# control_board.net
KiCad netlist of a schematic drawn in EAGLE
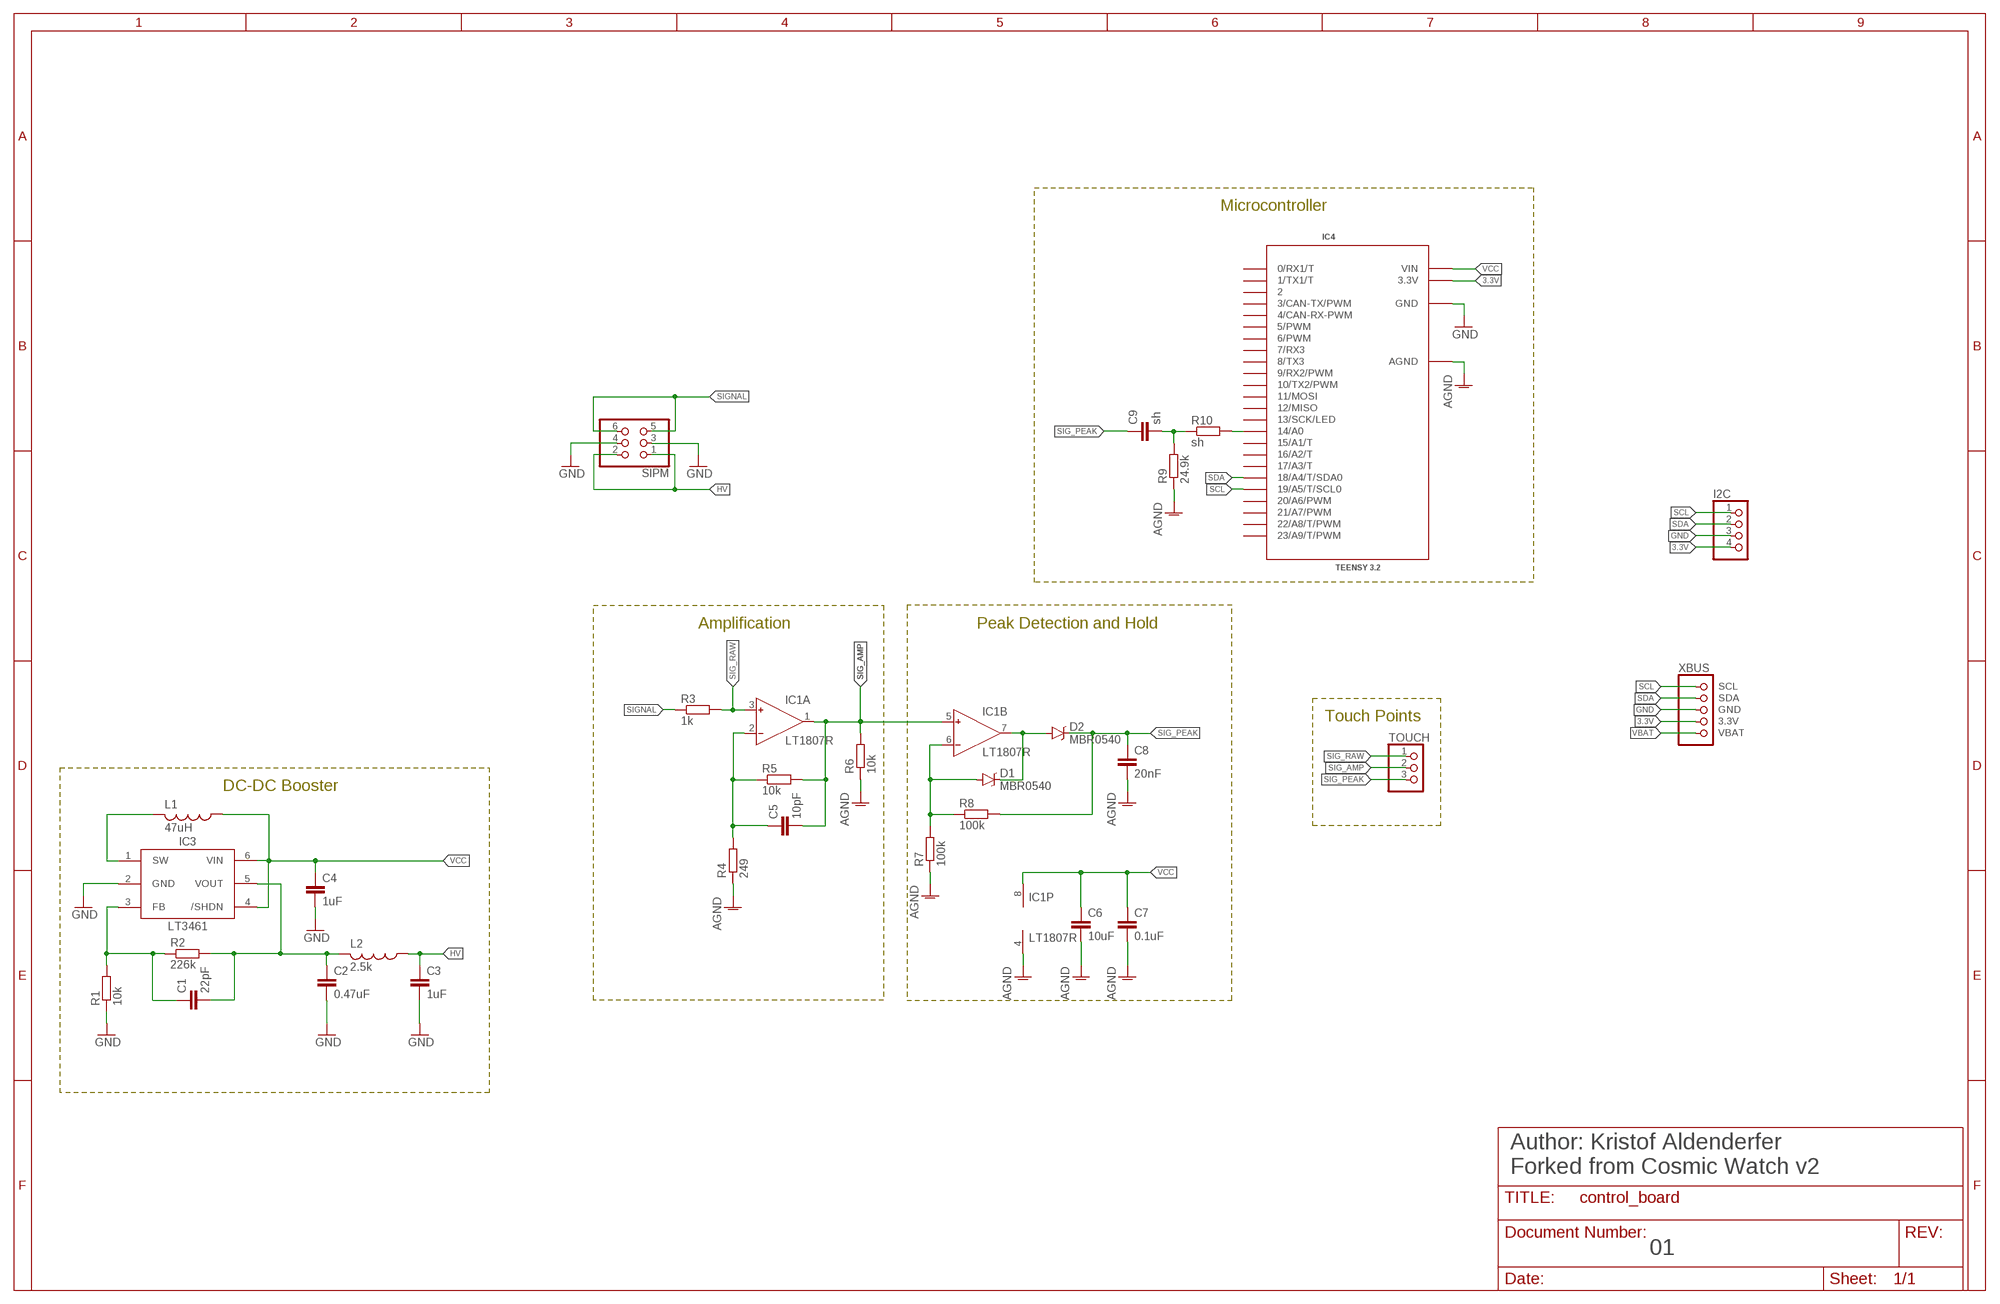
[diagram p0: schematic, sheet 1]

(export (version "E")
  (design (tool "Eeschema 10.0.6"))
  (components
    (comp (ref "C1")
      (value "22pF")
      (footprint "eagle-import:C0805K")
      (libsource (lib "eagle-import") (part "C-EUC0805K"))
    )
    (comp (ref "C2")
      (value "0.47uF")
      (footprint "eagle-import:C0805K")
      (libsource (lib "eagle-import") (part "C-EUC0805K"))
    )
    (comp (ref "C3")
      (value "1uF")
      (footprint "eagle-import:C0805K")
      (libsource (lib "eagle-import") (part "C-EUC0805K"))
    )
    (comp (ref "C4")
      (value "1uF")
      (footprint "eagle-import:C0805K")
      (libsource (lib "eagle-import") (part "C-EUC0805K"))
    )
    (comp (ref "C5")
      (value "10pF")
      (footprint "eagle-import:C0805K")
      (libsource (lib "eagle-import") (part "C-EUC0805K"))
    )
    (comp (ref "C6")
      (value "10uF")
      (footprint "eagle-import:C0805K")
      (libsource (lib "eagle-import") (part "C-EUC0805K"))
    )
    (comp (ref "C7")
      (value "0.1uF")
      (footprint "eagle-import:C0805K")
      (libsource (lib "eagle-import") (part "C-EUC0805K"))
    )
    (comp (ref "C8")
      (value "20nF")
      (footprint "eagle-import:C0805K")
      (libsource (lib "eagle-import") (part "C-EUC0805K"))
    )
    (comp (ref "C9")
      (value "sh")
      (footprint "eagle-import:C0805K")
      (libsource (lib "eagle-import") (part "C-EUC0805K"))
    )
    (comp (ref "D1")
      (value "MBR0540")
      (footprint "eagle-import:SMA-DIODE")
      (libsource (lib "eagle-import") (part "DIODE-SCHOTTKY-B340A"))
    )
    (comp (ref "D2")
      (value "MBR0540")
      (footprint "eagle-import:SMA-DIODE")
      (libsource (lib "eagle-import") (part "DIODE-SCHOTTKY-B340A"))
    )
    (comp (ref "I2C")
      (value "PINHD-1X4")
      (footprint "eagle-import:1X04")
      (libsource (lib "eagle-import") (part "PINHD-1X4"))
    )
    (comp (ref "IC1")
      (value "LT1807R")
      (footprint "eagle-import:SO8")
      (fields (field (name "MF") "ALTERA CORPORATION") (field (name "MPN") "AD746JRZ"))
      (libsource (lib "eagle-import") (part "LT1807R"))
    )
    (comp (ref "IC3")
      (value "LT3461")
      (footprint "eagle-import:SOT23-6")
      (libsource (lib "eagle-import") (part "LT3461"))
    )
    (comp (ref "IC4")
      (value "TEENSY 3.2")
      (footprint "eagle-import:TEENSY_3.2_NO_BOTTOM")
      (libsource (lib "eagle-import") (part "TEENSY_3.2_NO_BOTTOM"))
    )
    (comp (ref "L1")
      (value "47uH")
      (footprint "eagle-import:L2012C")
      (libsource (lib "eagle-import") (part "L-USL2012C"))
    )
    (comp (ref "L2")
      (value "2.5k")
      (footprint "eagle-import:L2012C")
      (libsource (lib "eagle-import") (part "L-USL2012C"))
    )
    (comp (ref "R1")
      (value "10k")
      (footprint "eagle-import:M0805")
      (libsource (lib "eagle-import") (part "R-EU_M0805"))
    )
    (comp (ref "R2")
      (value "226k")
      (footprint "eagle-import:M0805")
      (libsource (lib "eagle-import") (part "R-EU_M0805"))
    )
    (comp (ref "R3")
      (value "1k")
      (footprint "eagle-import:M0805")
      (libsource (lib "eagle-import") (part "R-EU_M0805"))
    )
    (comp (ref "R4")
      (value "249")
      (footprint "eagle-import:M0805")
      (libsource (lib "eagle-import") (part "R-EU_M0805"))
    )
    (comp (ref "R5")
      (value "10k")
      (footprint "eagle-import:M0805")
      (libsource (lib "eagle-import") (part "R-EU_M0805"))
    )
    (comp (ref "R6")
      (value "10k")
      (footprint "eagle-import:M0805")
      (libsource (lib "eagle-import") (part "R-EU_M0805"))
    )
    (comp (ref "R7")
      (value "100k")
      (footprint "eagle-import:M0805")
      (libsource (lib "eagle-import") (part "R-EU_M0805"))
    )
    (comp (ref "R8")
      (value "100k")
      (footprint "eagle-import:M0805")
      (libsource (lib "eagle-import") (part "R-EU_M0805"))
    )
    (comp (ref "R9")
      (value "24.9k")
      (footprint "eagle-import:M0805")
      (libsource (lib "eagle-import") (part "R-EU_M0805"))
    )
    (comp (ref "R10")
      (value "sh")
      (footprint "eagle-import:M0805")
      (libsource (lib "eagle-import") (part "R-EU_M0805"))
    )
    (comp (ref "SIPM")
      (value "PINHD-2X3")
      (footprint "eagle-import:2X03")
      (libsource (lib "eagle-import") (part "PINHD-2X3"))
    )
    (comp (ref "TOUCH")
      (value "PINHD-1X3")
      (footprint "eagle-import:1X03")
      (libsource (lib "eagle-import") (part "PINHD-1X3"))
    )
    (comp (ref "XBUS")
      (value "XINABOX-XBUS")
      (footprint "eagle-import:XBUS_1X05_PAD")
      (libsource (lib "eagle-import") (part "XINABOX-XBUS"))
    )
  )
  (nets
    (net (code "1") (name "3.3V") (class "Default")
      (node (ref "I2C") (pin "4") (pinfunction "4_4") (pintype "passive"))
      (node (ref "IC4") (pin "3.3V") (pinfunction "3.3V_3.3V") (pintype "power_in"))
      (node (ref "XBUS") (pin "P4B") (pinfunction "3.3V_P4B") (pintype "passive"))
      (node (ref "XBUS") (pin "P4T") (pinfunction "3.3V_P4T") (pintype "passive"))
    )
    (net (code "2") (name "AGND") (class "Default")
      (node (ref "C6") (pin "2") (pinfunction "2_2") (pintype "passive"))
      (node (ref "C7") (pin "2") (pinfunction "2_2") (pintype "passive"))
      (node (ref "C8") (pin "2") (pinfunction "2_2") (pintype "passive"))
      (node (ref "IC1") (pin "4") (pinfunction "V-_4") (pintype "power_in"))
      (node (ref "IC4") (pin "AGND") (pinfunction "AGND_AGND") (pintype "power_in"))
      (node (ref "R4") (pin "1") (pinfunction "1_1") (pintype "passive"))
      (node (ref "R6") (pin "1") (pinfunction "1_1") (pintype "passive"))
      (node (ref "R7") (pin "1") (pinfunction "1_1") (pintype "passive"))
      (node (ref "R9") (pin "1") (pinfunction "1_1") (pintype "passive"))
    )
    (net (code "3") (name "GND") (class "Default")
      (node (ref "C2") (pin "2") (pinfunction "2_2") (pintype "passive"))
      (node (ref "C3") (pin "2") (pinfunction "2_2") (pintype "passive"))
      (node (ref "C4") (pin "2") (pinfunction "2_2") (pintype "passive"))
      (node (ref "I2C") (pin "3") (pinfunction "3_3") (pintype "passive"))
      (node (ref "IC3") (pin "2") (pinfunction "GND_2") (pintype "power_in"))
      (node (ref "IC4") (pin "GND") (pinfunction "GND_GND") (pintype "power_in"))
      (node (ref "R1") (pin "1") (pinfunction "1_1") (pintype "passive"))
      (node (ref "SIPM") (pin "3") (pinfunction "3_3") (pintype "passive"))
      (node (ref "SIPM") (pin "4") (pinfunction "4_4") (pintype "passive"))
      (node (ref "XBUS") (pin "P3B") (pinfunction "GND_P3B") (pintype "passive"))
      (node (ref "XBUS") (pin "P3T") (pinfunction "GND_P3T") (pintype "passive"))
    )
    (net (code "4") (name "HV") (class "Default")
      (node (ref "C3") (pin "1") (pinfunction "1_1") (pintype "passive"))
      (node (ref "L2") (pin "1") (pinfunction "1_1") (pintype "passive"))
      (node (ref "SIPM") (pin "1") (pinfunction "1_1") (pintype "passive"))
      (node (ref "SIPM") (pin "2") (pinfunction "2_2") (pintype "passive"))
    )
    (net (code "5") (name "Net-(C9-Pad2)") (class "Default")
      (node (ref "C9") (pin "2") (pinfunction "2_2") (pintype "passive"))
      (node (ref "R10") (pin "1") (pinfunction "1_1") (pintype "passive"))
      (node (ref "R9") (pin "2") (pinfunction "2_2") (pintype "passive"))
    )
    (net (code "6") (name "Net-(IC1A-IN-)") (class "Default")
      (node (ref "C5") (pin "1") (pinfunction "1_1") (pintype "passive"))
      (node (ref "IC1") (pin "2") (pinfunction "IN-_2") (pintype "input"))
      (node (ref "R4") (pin "2") (pinfunction "2_2") (pintype "passive"))
      (node (ref "R5") (pin "1") (pinfunction "1_1") (pintype "passive"))
    )
    (net (code "7") (name "Net-(IC1B-IN-)") (class "Default")
      (node (ref "D1") (pin "A") (pinfunction "A_A") (pintype "passive"))
      (node (ref "IC1") (pin "6") (pinfunction "IN-_6") (pintype "input"))
      (node (ref "R7") (pin "2") (pinfunction "2_2") (pintype "passive"))
      (node (ref "R8") (pin "1") (pinfunction "1_1") (pintype "passive"))
    )
    (net (code "8") (name "Net-(IC1B-OUT)") (class "Default")
      (node (ref "D1") (pin "C") (pinfunction "C_C") (pintype "passive"))
      (node (ref "D2") (pin "A") (pinfunction "A_A") (pintype "passive"))
      (node (ref "IC1") (pin "7") (pinfunction "OUT_7") (pintype "output"))
    )
    (net (code "9") (name "Net-(IC3-FB)") (class "Default")
      (node (ref "C1") (pin "1") (pinfunction "1_1") (pintype "passive"))
      (node (ref "IC3") (pin "3") (pinfunction "FB_3") (pintype "input"))
      (node (ref "R1") (pin "2") (pinfunction "2_2") (pintype "passive"))
      (node (ref "R2") (pin "1") (pinfunction "1_1") (pintype "passive"))
    )
    (net (code "10") (name "Net-(IC3-SW)") (class "Default")
      (node (ref "IC3") (pin "1") (pinfunction "SW_1") (pintype "output"))
      (node (ref "L1") (pin "2") (pinfunction "2_2") (pintype "passive"))
    )
    (net (code "11") (name "Net-(IC3-VOUT)") (class "Default")
      (node (ref "C1") (pin "2") (pinfunction "2_2") (pintype "passive"))
      (node (ref "C2") (pin "1") (pinfunction "1_1") (pintype "passive"))
      (node (ref "IC3") (pin "5") (pinfunction "VOUT_5") (pintype "output"))
      (node (ref "L2") (pin "2") (pinfunction "2_2") (pintype "passive"))
      (node (ref "R2") (pin "2") (pinfunction "2_2") (pintype "passive"))
    )
    (net (code "12") (name "Net-(IC4-Pad14{slash}A0)") (class "Default")
      (node (ref "IC4") (pin "14/A0") (pinfunction "14/A0_14/A0") (pintype "bidirectional"))
      (node (ref "R10") (pin "2") (pinfunction "2_2") (pintype "passive"))
    )
    (net (code "13") (name "SCL") (class "Default")
      (node (ref "I2C") (pin "1") (pinfunction "1_1") (pintype "passive"))
      (node (ref "IC4") (pin "19/A5") (pinfunction "19/A5/T/SCL0_19/A5") (pintype "bidirectional"))
      (node (ref "XBUS") (pin "P1B") (pinfunction "SCL_P1B") (pintype "passive"))
      (node (ref "XBUS") (pin "P1T") (pinfunction "SCL_P1T") (pintype "passive"))
    )
    (net (code "14") (name "SDA") (class "Default")
      (node (ref "I2C") (pin "2") (pinfunction "2_2") (pintype "passive"))
      (node (ref "IC4") (pin "18/A4") (pinfunction "18/A4/T/SDA0_18/A4") (pintype "bidirectional"))
      (node (ref "XBUS") (pin "P2B") (pinfunction "SDA_P2B") (pintype "passive"))
      (node (ref "XBUS") (pin "P2T") (pinfunction "SDA_P2T") (pintype "passive"))
    )
    (net (code "15") (name "SIGNAL") (class "Default")
      (node (ref "R3") (pin "1") (pinfunction "1_1") (pintype "passive"))
      (node (ref "SIPM") (pin "5") (pinfunction "5_5") (pintype "passive"))
      (node (ref "SIPM") (pin "6") (pinfunction "6_6") (pintype "passive"))
    )
    (net (code "16") (name "SIG_AMP") (class "Default")
      (node (ref "C5") (pin "2") (pinfunction "2_2") (pintype "passive"))
      (node (ref "IC1") (pin "1") (pinfunction "OUT_1") (pintype "output"))
      (node (ref "IC1") (pin "5") (pinfunction "IN+_5") (pintype "input"))
      (node (ref "R5") (pin "2") (pinfunction "2_2") (pintype "passive"))
      (node (ref "R6") (pin "2") (pinfunction "2_2") (pintype "passive"))
      (node (ref "TOUCH") (pin "2") (pinfunction "2_2") (pintype "passive"))
    )
    (net (code "17") (name "SIG_PEAK") (class "Default")
      (node (ref "C8") (pin "1") (pinfunction "1_1") (pintype "passive"))
      (node (ref "C9") (pin "1") (pinfunction "1_1") (pintype "passive"))
      (node (ref "D2") (pin "C") (pinfunction "C_C") (pintype "passive"))
      (node (ref "R8") (pin "2") (pinfunction "2_2") (pintype "passive"))
      (node (ref "TOUCH") (pin "3") (pinfunction "3_3") (pintype "passive"))
    )
    (net (code "18") (name "SIG_RAW") (class "Default")
      (node (ref "IC1") (pin "3") (pinfunction "IN+_3") (pintype "input"))
      (node (ref "R3") (pin "2") (pinfunction "2_2") (pintype "passive"))
      (node (ref "TOUCH") (pin "1") (pinfunction "1_1") (pintype "passive"))
    )
    (net (code "19") (name "VBAT") (class "Default")
      (node (ref "XBUS") (pin "P5B") (pinfunction "VBAT_P5B") (pintype "passive"))
      (node (ref "XBUS") (pin "P5T") (pinfunction "VBAT_P5T") (pintype "passive"))
    )
    (net (code "20") (name "VCC") (class "Default")
      (node (ref "C4") (pin "1") (pinfunction "1_1") (pintype "passive"))
      (node (ref "C6") (pin "1") (pinfunction "1_1") (pintype "passive"))
      (node (ref "C7") (pin "1") (pinfunction "1_1") (pintype "passive"))
      (node (ref "IC1") (pin "8") (pinfunction "V+_8") (pintype "power_in"))
      (node (ref "IC3") (pin "4") (pinfunction "/SHDN_4") (pintype "input"))
      (node (ref "IC3") (pin "6") (pinfunction "VIN_6") (pintype "input"))
      (node (ref "IC4") (pin "VIN") (pinfunction "VIN_VIN") (pintype "power_in"))
      (node (ref "L1") (pin "1") (pinfunction "1_1") (pintype "passive"))
    )
    (net (code "21") (name "unconnected-(IC4-0{slash}RX1{slash}T-Pad0)") (class "Default")
      (node (ref "IC4") (pin "0") (pinfunction "0/RX1/T_0") (pintype "bidirectional"))
    )
    (net (code "22") (name "unconnected-(IC4-1{slash}TX1{slash}T-Pad1)") (class "Default")
      (node (ref "IC4") (pin "1") (pinfunction "1/TX1/T_1") (pintype "bidirectional"))
    )
    (net (code "23") (name "unconnected-(IC4-3{slash}CAN-TX{slash}PWM-Pad3)") (class "Default")
      (node (ref "IC4") (pin "3") (pinfunction "3/CAN-TX/PWM_3") (pintype "bidirectional"))
    )
    (net (code "24") (name "unconnected-(IC4-4{slash}CAN-RX-PWM-Pad4)") (class "Default")
      (node (ref "IC4") (pin "4") (pinfunction "4/CAN-RX-PWM_4") (pintype "bidirectional"))
    )
    (net (code "25") (name "unconnected-(IC4-5{slash}PWM-Pad5)") (class "Default")
      (node (ref "IC4") (pin "5") (pinfunction "5/PWM_5") (pintype "bidirectional"))
    )
    (net (code "26") (name "unconnected-(IC4-6{slash}PWM-Pad6)") (class "Default")
      (node (ref "IC4") (pin "6") (pinfunction "6/PWM_6") (pintype "bidirectional"))
    )
    (net (code "27") (name "unconnected-(IC4-7{slash}RX3-Pad7)") (class "Default")
      (node (ref "IC4") (pin "7") (pinfunction "7/RX3_7") (pintype "bidirectional"))
    )
    (net (code "28") (name "unconnected-(IC4-8{slash}TX3-Pad8)") (class "Default")
      (node (ref "IC4") (pin "8") (pinfunction "8/TX3_8") (pintype "bidirectional"))
    )
    (net (code "29") (name "unconnected-(IC4-9{slash}RX2{slash}PWM-Pad9)") (class "Default")
      (node (ref "IC4") (pin "9") (pinfunction "9/RX2/PWM_9") (pintype "bidirectional"))
    )
    (net (code "30") (name "unconnected-(IC4-10{slash}TX2{slash}PWM-Pad10)") (class "Default")
      (node (ref "IC4") (pin "10") (pinfunction "10/TX2/PWM_10") (pintype "bidirectional"))
    )
    (net (code "31") (name "unconnected-(IC4-11{slash}MOSI-Pad11)") (class "Default")
      (node (ref "IC4") (pin "11") (pinfunction "11/MOSI_11") (pintype "bidirectional"))
    )
    (net (code "32") (name "unconnected-(IC4-12{slash}MISO-Pad12)") (class "Default")
      (node (ref "IC4") (pin "12") (pinfunction "12/MISO_12") (pintype "bidirectional"))
    )
    (net (code "33") (name "unconnected-(IC4-13{slash}SCK{slash}LED-Pad13)") (class "Default")
      (node (ref "IC4") (pin "13") (pinfunction "13/SCK/LED_13") (pintype "bidirectional"))
    )
    (net (code "34") (name "unconnected-(IC4-15{slash}A1{slash}T-Pad15{slash}A1)") (class "Default")
      (node (ref "IC4") (pin "15/A1") (pinfunction "15/A1/T_15/A1") (pintype "bidirectional"))
    )
    (net (code "35") (name "unconnected-(IC4-16{slash}A2{slash}T-Pad16{slash}A2)") (class "Default")
      (node (ref "IC4") (pin "16/A2") (pinfunction "16/A2/T_16/A2") (pintype "bidirectional"))
    )
    (net (code "36") (name "unconnected-(IC4-17{slash}A3{slash}T-Pad17{slash}A3)") (class "Default")
      (node (ref "IC4") (pin "17/A3") (pinfunction "17/A3/T_17/A3") (pintype "bidirectional"))
    )
    (net (code "37") (name "unconnected-(IC4-20{slash}A6{slash}PWM-Pad20{slash}A6)") (class "Default")
      (node (ref "IC4") (pin "20/A6") (pinfunction "20/A6/PWM_20/A6") (pintype "bidirectional"))
    )
    (net (code "38") (name "unconnected-(IC4-21{slash}A7{slash}PWM-Pad21{slash}A7)") (class "Default")
      (node (ref "IC4") (pin "21/A7") (pinfunction "21/A7/PWM_21/A7") (pintype "bidirectional"))
    )
    (net (code "39") (name "unconnected-(IC4-22{slash}A8{slash}T{slash}PWM-Pad22{slash}A8)") (class "Default")
      (node (ref "IC4") (pin "22/A8") (pinfunction "22/A8/T/PWM_22/A8") (pintype "bidirectional"))
    )
    (net (code "40") (name "unconnected-(IC4-23{slash}A9{slash}T{slash}PWM-Pad23{slash}A9)") (class "Default")
      (node (ref "IC4") (pin "23/A9") (pinfunction "23/A9/T/PWM_23/A9") (pintype "bidirectional"))
    )
    (net (code "41") (name "unconnected-(IC4-Pad2)") (class "Default")
      (node (ref "IC4") (pin "2") (pinfunction "2_2") (pintype "bidirectional"))
    )
  )
)
